# QCopterFC_FFC_Sch.net
KiCad netlist of a schematic drawn in Altium Designer
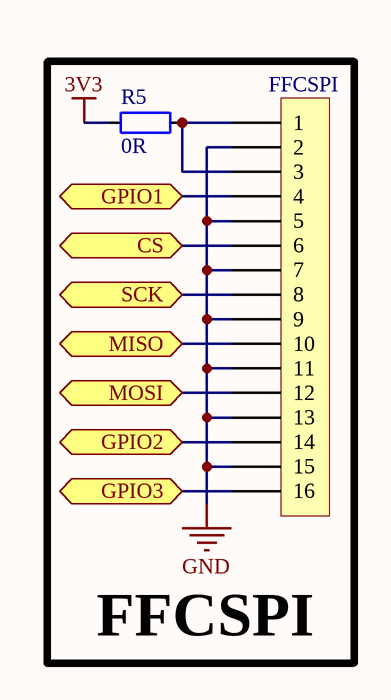
[diagram p0: QCopterFC_FFC_Sch.SchDoc]

(export (version "E")
  (design (tool "Eeschema 10.0.6"))
  (components
    (comp (ref "FFCSPI")
      (value "FFC_0.5_16")
      (footprint "PCB_Connector:FFC_0.5_16")
      (description "FFC")
      (libsource (lib "SCH_Connector") (part "FFC_0.5_16"))
    )
    (comp (ref "R5")
      (value "0R")
      (footprint "PCB_Passive:RES_0603")
      (description "Resistor")
      (fields (field (name "Comment") "Res_0603"))
      (libsource (lib "SCH_Passive") (part "Res_0603"))
    )
  )
  (nets
    (net (code "1") (name "/CS") (class "Default")
      (node (ref "FFCSPI") (pin "6") (pinfunction "6_6") (pintype "passive"))
    )
    (net (code "2") (name "/GPIO1") (class "Default")
      (node (ref "FFCSPI") (pin "4") (pinfunction "4_4") (pintype "passive"))
    )
    (net (code "3") (name "/GPIO2") (class "Default")
      (node (ref "FFCSPI") (pin "14") (pinfunction "14_14") (pintype "passive"))
    )
    (net (code "4") (name "/GPIO3") (class "Default")
      (node (ref "FFCSPI") (pin "16") (pinfunction "16_16") (pintype "passive"))
    )
    (net (code "5") (name "/MISO") (class "Default")
      (node (ref "FFCSPI") (pin "10") (pinfunction "10_10") (pintype "passive"))
    )
    (net (code "6") (name "/MOSI") (class "Default")
      (node (ref "FFCSPI") (pin "12") (pinfunction "12_12") (pintype "passive"))
    )
    (net (code "7") (name "/SCK") (class "Default")
      (node (ref "FFCSPI") (pin "8") (pinfunction "8_8") (pintype "passive"))
    )
    (net (code "8") (name "3V3") (class "Default")
      (node (ref "R5") (pin "1") (pinfunction "1_1") (pintype "passive"))
    )
    (net (code "9") (name "GND") (class "Default")
      (node (ref "FFCSPI") (pin "11") (pinfunction "11_11") (pintype "passive"))
      (node (ref "FFCSPI") (pin "13") (pinfunction "13_13") (pintype "passive"))
      (node (ref "FFCSPI") (pin "15") (pinfunction "15_15") (pintype "passive"))
      (node (ref "FFCSPI") (pin "2") (pinfunction "2_2") (pintype "passive"))
      (node (ref "FFCSPI") (pin "5") (pinfunction "5_5") (pintype "passive"))
      (node (ref "FFCSPI") (pin "7") (pinfunction "7_7") (pintype "passive"))
      (node (ref "FFCSPI") (pin "9") (pinfunction "9_9") (pintype "passive"))
    )
    (net (code "10") (name "Net-(FFCSPI-Pad1)") (class "Default")
      (node (ref "FFCSPI") (pin "1") (pinfunction "1_1") (pintype "passive"))
      (node (ref "FFCSPI") (pin "3") (pinfunction "3_3") (pintype "passive"))
      (node (ref "R5") (pin "2") (pinfunction "2_2") (pintype "passive"))
    )
  )
)
